# TITAN_ADAPTER.net
KiCad netlist of a schematic drawn in Altium Designer
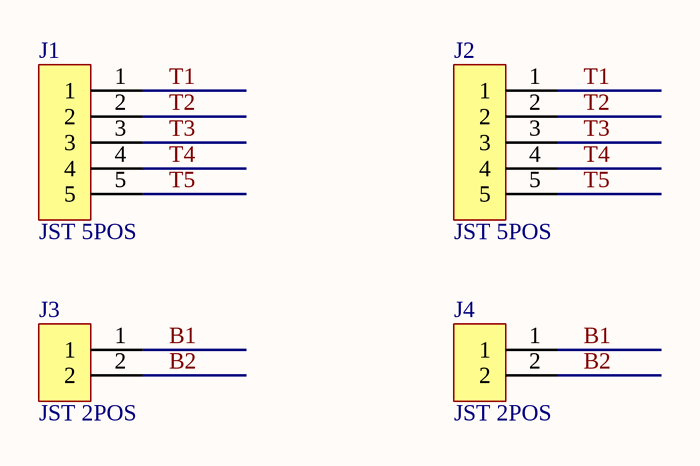
[diagram p0: TITAN_ADAPTER.SchDoc]

(export (version "E")
  (design (tool "Eeschema 10.0.6"))
  (components
    (comp (ref "J1")
      (value "JST 5POS")
      (footprint "JST-5")
      (description "CONN HEADER SMD R/A 5POS 1MM, side mount")
      (fields
        (field (name "MANUFACTURER") "JST")
        (field (name "MANUFACTURER PART NUMBER") "SM05B-SRSS-TB(LF)(SN)")
      )
      (libsource (lib "TITAN_ADAPTER") (part "SM05B-SRSS-TB(LF)(SN)"))
    )
    (comp (ref "J2")
      (value "JST 5POS")
      (footprint "JST-5")
      (description "CONN HEADER SMD R/A 5POS 1MM, side mount")
      (fields
        (field (name "MANUFACTURER") "JST")
        (field (name "MANUFACTURER PART NUMBER") "SM05B-SRSS-TB(LF)(SN)")
      )
      (libsource (lib "TITAN_ADAPTER") (part "SM05B-SRSS-TB(LF)(SN)"))
    )
    (comp (ref "J3")
      (value "JST 2POS")
      (footprint "JST-2")
      (description "Conn Shrouded Header HDR 2 POS 1mm Solder RA SMD T/R, side mount")
      (fields
        (field (name "MANUFACTURER") "JST")
        (field (name "MANUFACTURER PART NUMBER") "SM02B-SRSS-TB(LF)(SN)")
      )
      (libsource (lib "TITAN_ADAPTER") (part "SM02B-SRSS-TB(LF)(SN)"))
    )
    (comp (ref "J4")
      (value "JST 2POS")
      (footprint "JST-2")
      (description "Conn Shrouded Header HDR 2 POS 1mm Solder RA SMD T/R, side mount")
      (fields
        (field (name "MANUFACTURER") "JST")
        (field (name "MANUFACTURER PART NUMBER") "SM02B-SRSS-TB(LF)(SN)")
      )
      (libsource (lib "TITAN_ADAPTER") (part "SM02B-SRSS-TB(LF)(SN)"))
    )
  )
  (nets
    (net (code "1") (name "/B1") (class "Default")
      (node (ref "J3") (pin "1") (pinfunction "1_1") (pintype "passive"))
      (node (ref "J4") (pin "1") (pinfunction "1_1") (pintype "passive"))
    )
    (net (code "2") (name "/B2") (class "Default")
      (node (ref "J3") (pin "2") (pinfunction "2_2") (pintype "passive"))
      (node (ref "J4") (pin "2") (pinfunction "2_2") (pintype "passive"))
    )
    (net (code "3") (name "/T1") (class "Default")
      (node (ref "J1") (pin "1") (pinfunction "1_1") (pintype "passive"))
      (node (ref "J2") (pin "1") (pinfunction "1_1") (pintype "passive"))
    )
    (net (code "4") (name "/T2") (class "Default")
      (node (ref "J1") (pin "2") (pinfunction "2_2") (pintype "passive"))
      (node (ref "J2") (pin "2") (pinfunction "2_2") (pintype "passive"))
    )
    (net (code "5") (name "/T3") (class "Default")
      (node (ref "J1") (pin "3") (pinfunction "3_3") (pintype "passive"))
      (node (ref "J2") (pin "3") (pinfunction "3_3") (pintype "passive"))
    )
    (net (code "6") (name "/T4") (class "Default")
      (node (ref "J1") (pin "4") (pinfunction "4_4") (pintype "passive"))
      (node (ref "J2") (pin "4") (pinfunction "4_4") (pintype "passive"))
    )
    (net (code "7") (name "/T5") (class "Default")
      (node (ref "J1") (pin "5") (pinfunction "5_5") (pintype "passive"))
      (node (ref "J2") (pin "5") (pinfunction "5_5") (pintype "passive"))
    )
  )
)
